# DHT11.net
KiCad netlist of a schematic drawn in Altium Designer
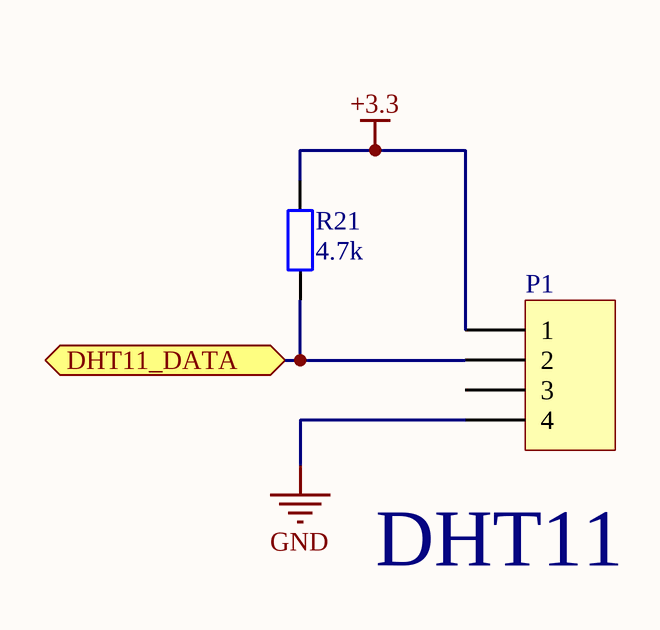
[diagram p0: DHT11.SchDoc]

(export (version "E")
  (design (tool "Eeschema 10.0.6"))
  (components
    (comp (ref "P1")
      (value "DHT11")
      (footprint "HDR1X4H")
      (description "Header, 4-Pin, Right Angle")
      (fields (field (name "PUBLISHER") "Altium Limited"))
      (libsource (lib "Miscellaneous Connectors") (part "Header 4H"))
    )
    (comp (ref "R21")
      (value "4.7k")
      (footprint "tro smd 0603")
      (description "Dán")
      (libsource (lib "Altium_Lib_by_KhueNguyenCreator") (part "Tro 0603 5% 4.7k"))
    )
  )
  (nets
    (net (code "1") (name "+3.3") (class "Default")
      (node (ref "P1") (pin "1") (pinfunction "1_1") (pintype "passive"))
      (node (ref "R21") (pin "2") (pinfunction "2_2") (pintype "passive"))
    )
    (net (code "2") (name "/DHT11_DATA") (class "Default")
      (node (ref "P1") (pin "2") (pinfunction "2_2") (pintype "passive"))
      (node (ref "R21") (pin "1") (pinfunction "1_1") (pintype "passive"))
    )
    (net (code "3") (name "GND") (class "Default")
      (node (ref "P1") (pin "4") (pinfunction "4_4") (pintype "passive"))
    )
    (net (code "4") (name "unconnected-(P1-Pad3)") (class "Default")
      (node (ref "P1") (pin "3") (pinfunction "3_3") (pintype "passive"))
    )
  )
)
